# kfly_v3_2.net
KiCad netlist of a schematic drawn in EAGLE
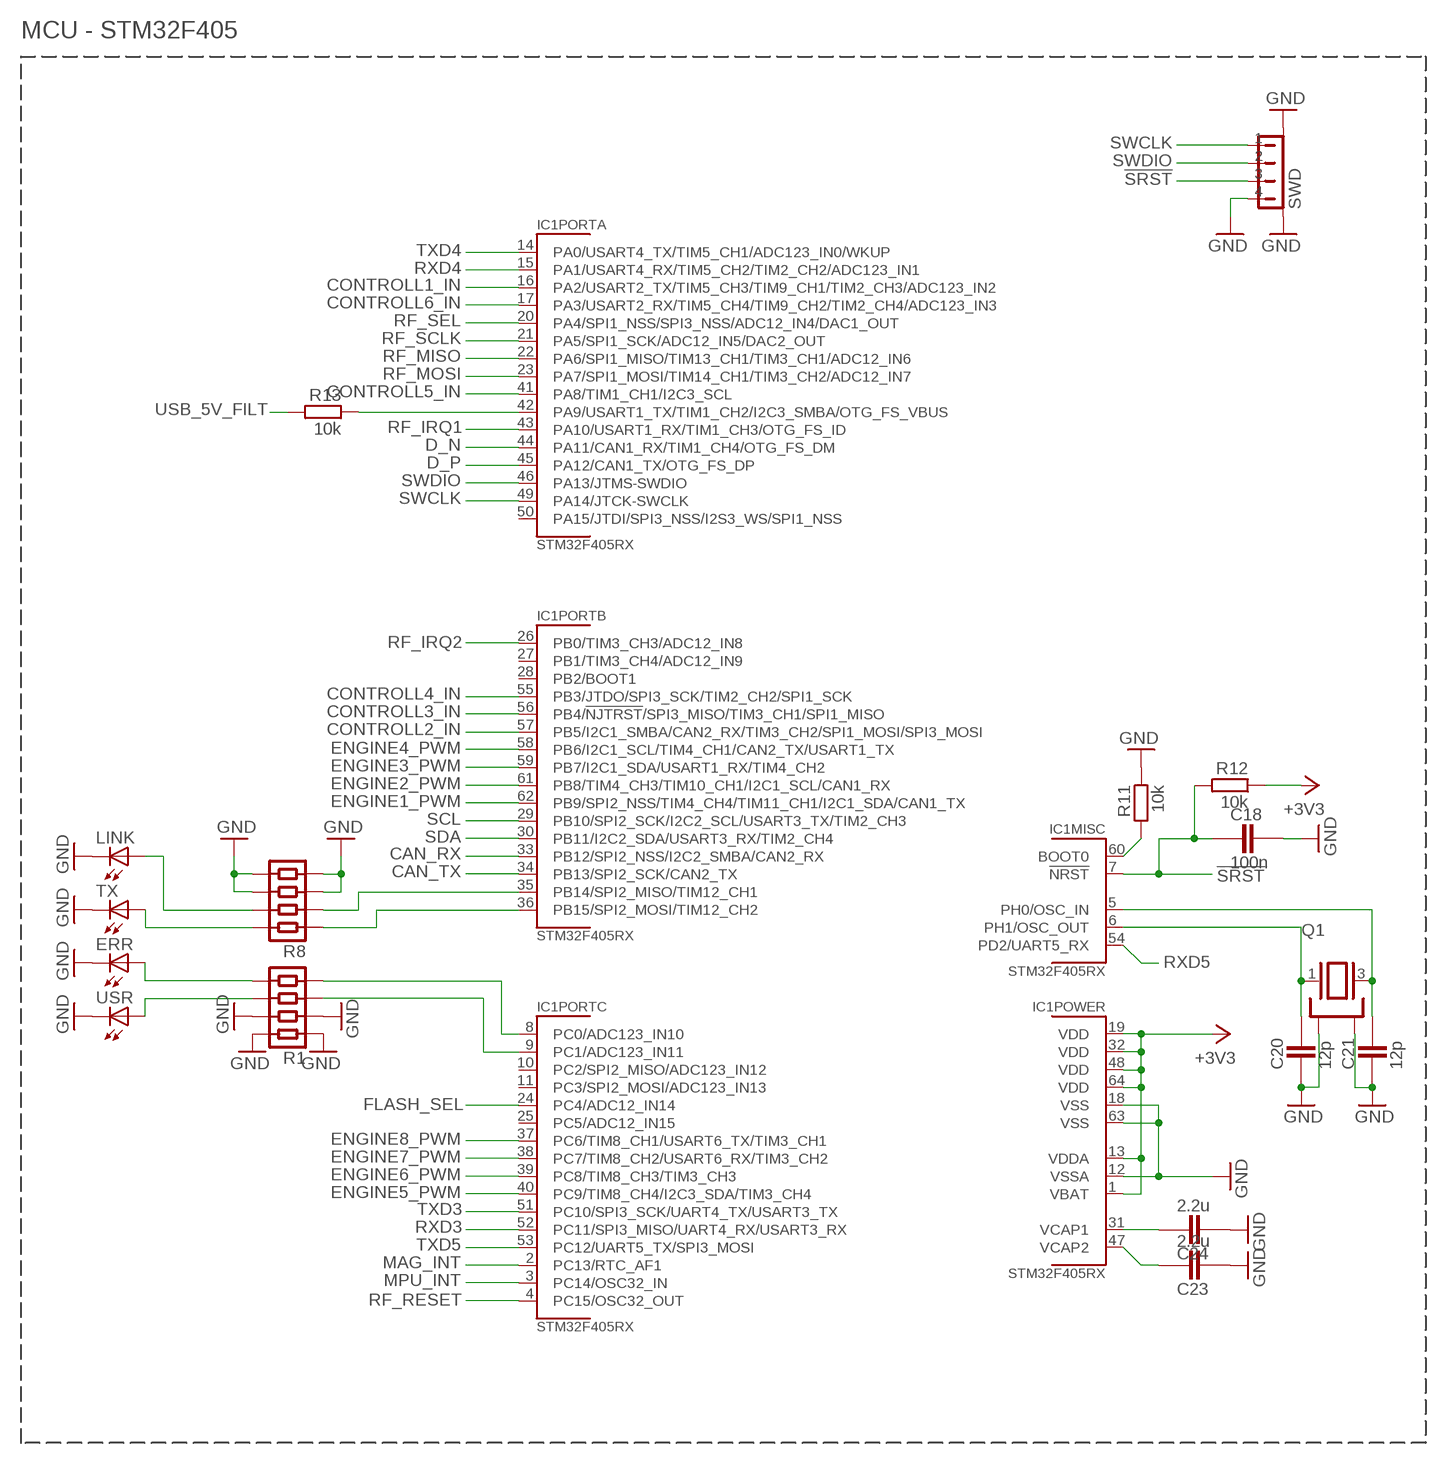
[diagram p0: schematic, sheet 1]
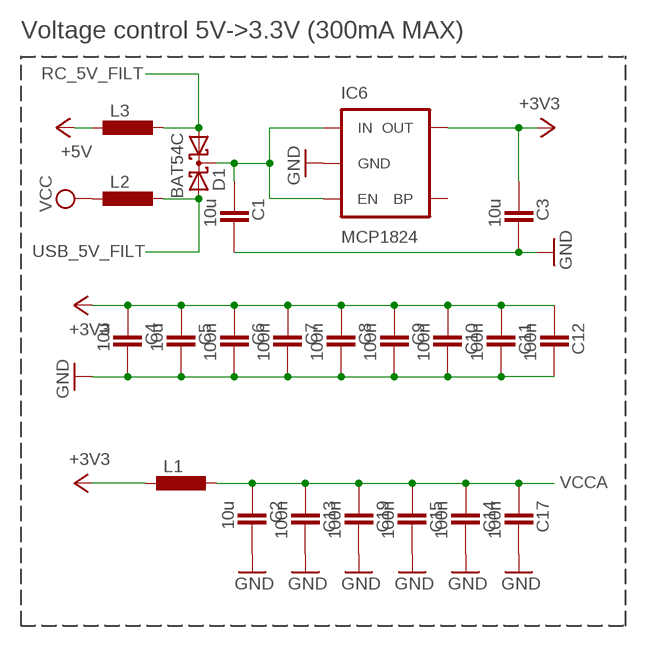
[diagram p1: schematic, sheet 2]
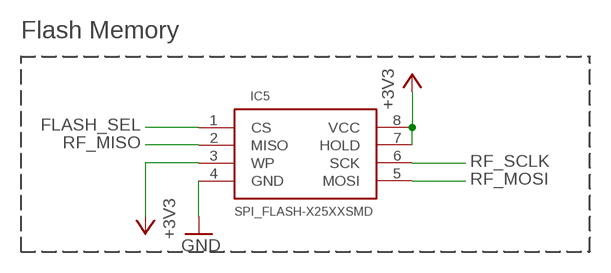
[diagram p2: schematic, sheet 3]
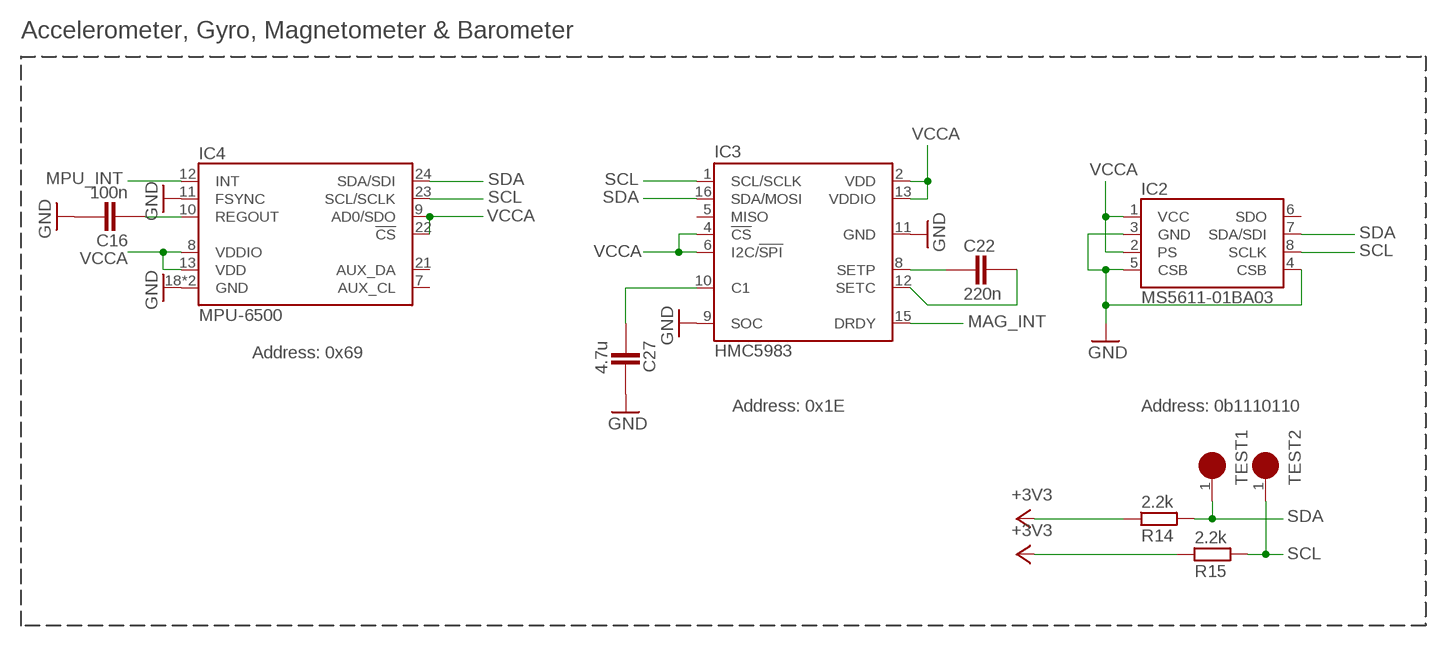
[diagram p3: schematic, sheet 4]
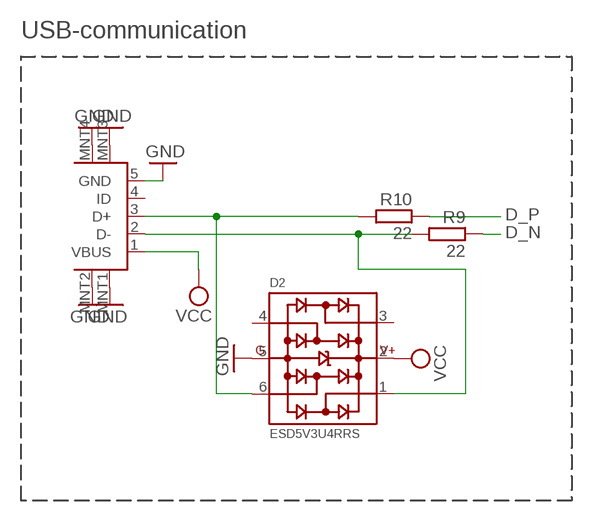
[diagram p4: schematic, sheet 5]
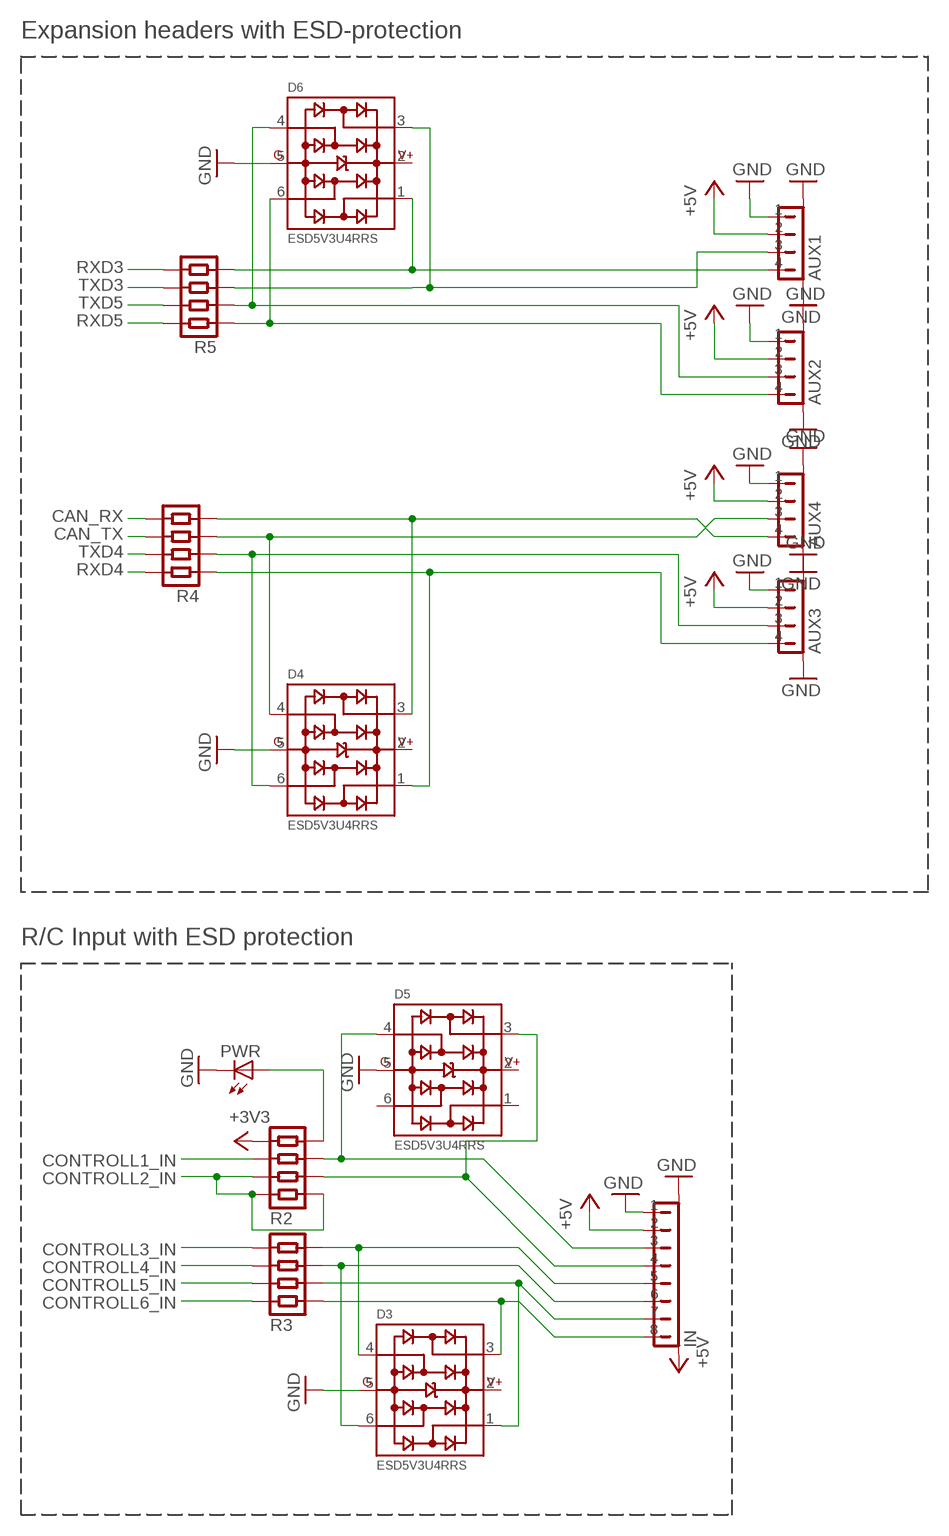
[diagram p5: schematic, sheet 6]
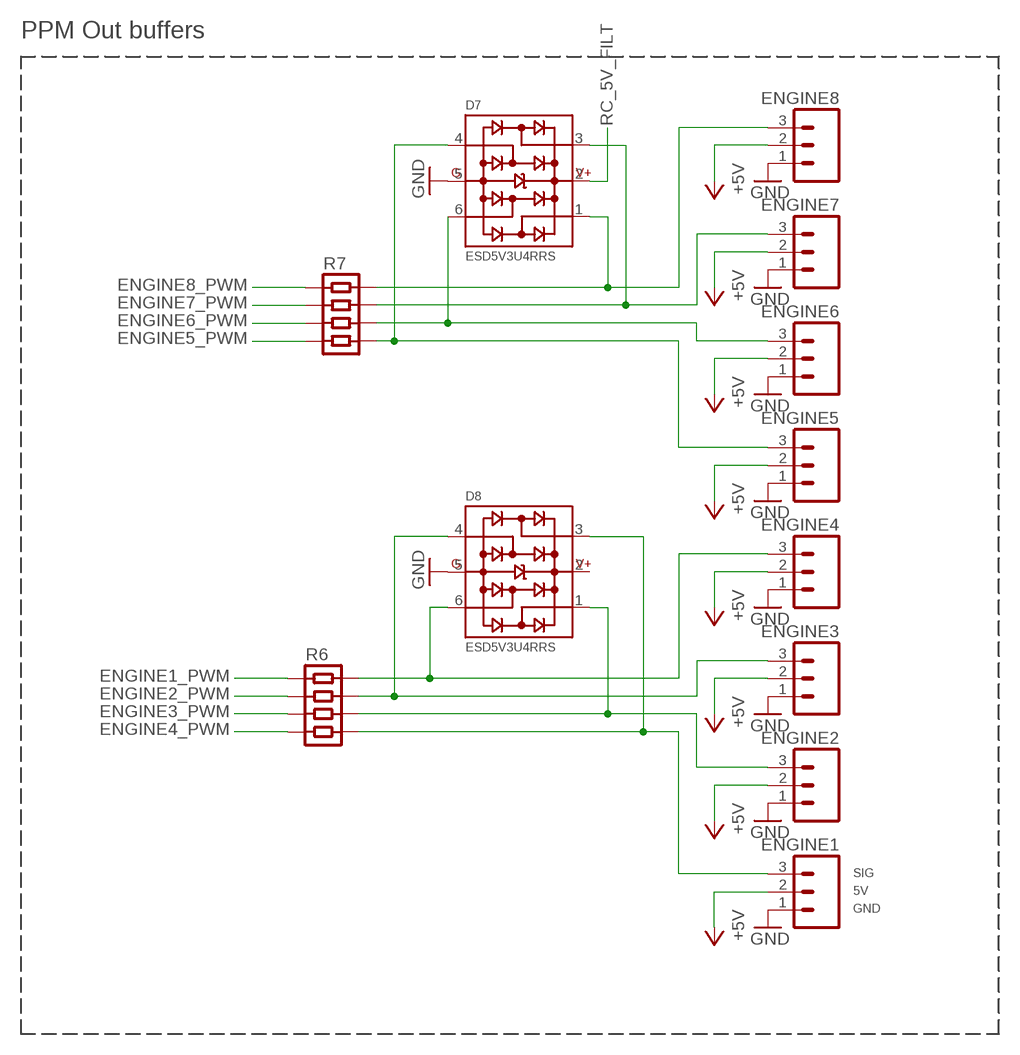
[diagram p6: schematic, sheet 7]
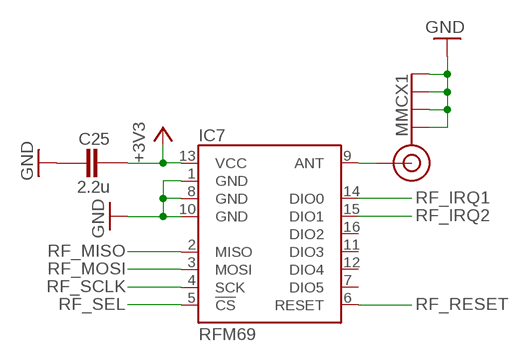
[diagram p7: schematic, sheet 8]

(export (version "E")
  (design (tool "Eeschema 10.0.6"))
  (components
    (comp (ref "C1")
      (value "10u")
      (footprint "eagle-import:CAPC1608X92N")
      (libsource (lib "eagle-import") (part "CAPACITOR_0603"))
    )
    (comp (ref "C2")
      (value "10u")
      (footprint "eagle-import:CAPC1608X92N")
      (libsource (lib "eagle-import") (part "CAPACITOR_0603"))
    )
    (comp (ref "C3")
      (value "10u")
      (footprint "eagle-import:CAPC1608X92N")
      (libsource (lib "eagle-import") (part "CAPACITOR_0603"))
    )
    (comp (ref "C4")
      (value "10u")
      (footprint "eagle-import:CAPC1608X92N")
      (libsource (lib "eagle-import") (part "CAPACITOR_0603"))
    )
    (comp (ref "C5")
      (value "10u")
      (footprint "eagle-import:CAPC1608X92N")
      (libsource (lib "eagle-import") (part "CAPACITOR_0603"))
    )
    (comp (ref "C6")
      (value "100n")
      (footprint "eagle-import:CAPC1005X60N")
      (libsource (lib "eagle-import") (part "CAPACITOR_0402"))
    )
    (comp (ref "C7")
      (value "100n")
      (footprint "eagle-import:CAPC1005X60N")
      (libsource (lib "eagle-import") (part "CAPACITOR_0402"))
    )
    (comp (ref "C8")
      (value "100n")
      (footprint "eagle-import:CAPC1005X60N")
      (libsource (lib "eagle-import") (part "CAPACITOR_0402"))
    )
    (comp (ref "C9")
      (value "100n")
      (footprint "eagle-import:CAPC1005X60N")
      (libsource (lib "eagle-import") (part "CAPACITOR_0402"))
    )
    (comp (ref "C10")
      (value "100n")
      (footprint "eagle-import:CAPC1005X60N")
      (libsource (lib "eagle-import") (part "CAPACITOR_0402"))
    )
    (comp (ref "C11")
      (value "100n")
      (footprint "eagle-import:CAPC1005X60N")
      (libsource (lib "eagle-import") (part "CAPACITOR_0402"))
    )
    (comp (ref "C12")
      (value "100n")
      (footprint "eagle-import:CAPC1005X60N")
      (libsource (lib "eagle-import") (part "CAPACITOR_0402"))
    )
    (comp (ref "C13")
      (value "100n")
      (footprint "eagle-import:CAPC1005X60N")
      (libsource (lib "eagle-import") (part "CAPACITOR_0402"))
    )
    (comp (ref "C14")
      (value "100n")
      (footprint "eagle-import:CAPC1005X60N")
      (libsource (lib "eagle-import") (part "CAPACITOR_0402"))
    )
    (comp (ref "C15")
      (value "100n")
      (footprint "eagle-import:CAPC1005X60N")
      (libsource (lib "eagle-import") (part "CAPACITOR_0402"))
    )
    (comp (ref "C17")
      (value "100n")
      (footprint "eagle-import:CAPC1005X60N")
      (libsource (lib "eagle-import") (part "CAPACITOR_0402"))
    )
    (comp (ref "C19")
      (value "100n")
      (footprint "eagle-import:CAPC1005X60N")
      (libsource (lib "eagle-import") (part "CAPACITOR_0402"))
    )
    (comp (ref "D1")
      (value "BAT54C")
      (footprint "eagle-import:SOT23")
      (libsource (lib "eagle-import") (part "BAT54C"))
    )
    (comp (ref "IC6")
      (value "MCP1824")
      (footprint "eagle-import:SOT23-5")
      (libsource (lib "eagle-import") (part "V_REG_LDOSMD"))
    )
    (comp (ref "L1")
      (value "INDUCTOR_0603")
      (footprint "eagle-import:INDC1608X95N")
      (libsource (lib "eagle-import") (part "INDUCTOR_0603"))
    )
    (comp (ref "L2")
      (value "INDUCTOR_0603")
      (footprint "eagle-import:INDC1608X95N")
      (libsource (lib "eagle-import") (part "INDUCTOR_0603"))
    )
    (comp (ref "L3")
      (value "INDUCTOR_0603")
      (footprint "eagle-import:INDC1608X95N")
      (libsource (lib "eagle-import") (part "INDUCTOR_0603"))
    )
    (comp (ref "AUX1")
      (value "JST-4PIN-SIDE-1.0")
      (footprint "eagle-import:JST-4PIN-SIDE")
      (libsource (lib "eagle-import") (part "JST-4PIN-SIDE-1.0"))
    )
    (comp (ref "AUX2")
      (value "JST-4PIN-SIDE-1.0")
      (footprint "eagle-import:JST-4PIN-SIDE")
      (libsource (lib "eagle-import") (part "JST-4PIN-SIDE-1.0"))
    )
    (comp (ref "AUX3")
      (value "JST-4PIN-SIDE-1.0")
      (footprint "eagle-import:JST-4PIN-SIDE")
      (libsource (lib "eagle-import") (part "JST-4PIN-SIDE-1.0"))
    )
    (comp (ref "AUX4")
      (value "JST-4PIN-SIDE-1.0")
      (footprint "eagle-import:JST-4PIN-SIDE")
      (libsource (lib "eagle-import") (part "JST-4PIN-SIDE-1.0"))
    )
    (comp (ref "D3")
      (value "ESD5V3U4RRS")
      (footprint "eagle-import:SOT363")
      (libsource (lib "eagle-import") (part "ESD5V3U4RRS"))
    )
    (comp (ref "D4")
      (value "ESD5V3U4RRS")
      (footprint "eagle-import:SOT363")
      (libsource (lib "eagle-import") (part "ESD5V3U4RRS"))
    )
    (comp (ref "D5")
      (value "ESD5V3U4RRS")
      (footprint "eagle-import:SOT363")
      (libsource (lib "eagle-import") (part "ESD5V3U4RRS"))
    )
    (comp (ref "D6")
      (value "ESD5V3U4RRS")
      (footprint "eagle-import:SOT363")
      (libsource (lib "eagle-import") (part "ESD5V3U4RRS"))
    )
    (comp (ref "IN")
      (value "JST-8PIN-SIDE-1.0")
      (footprint "eagle-import:JST-8PIN-SIDE")
      (libsource (lib "eagle-import") (part "JST-8PIN-SIDE-1.0"))
    )
    (comp (ref "PWR")
      (value "LED0603")
      (footprint "eagle-import:LED-0603")
      (libsource (lib "eagle-import") (part "LED0603"))
    )
    (comp (ref "R2")
      (value "RESISTOR-4ARRAY-0804")
      (footprint "eagle-import:RESISTORARRAY_0804")
      (libsource (lib "eagle-import") (part "RESISTOR-4ARRAY-0804"))
    )
    (comp (ref "R3")
      (value "RESISTOR-4ARRAY-0804")
      (footprint "eagle-import:RESISTORARRAY_0804")
      (libsource (lib "eagle-import") (part "RESISTOR-4ARRAY-0804"))
    )
    (comp (ref "R4")
      (value "RESISTOR-4ARRAY-0804")
      (footprint "eagle-import:RESISTORARRAY_0804")
      (libsource (lib "eagle-import") (part "RESISTOR-4ARRAY-0804"))
    )
    (comp (ref "R5")
      (value "RESISTOR-4ARRAY-0804")
      (footprint "eagle-import:RESISTORARRAY_0804")
      (libsource (lib "eagle-import") (part "RESISTOR-4ARRAY-0804"))
    )
    (comp (ref "C16")
      (value "100n")
      (footprint "eagle-import:CAPC1005X60N")
      (libsource (lib "eagle-import") (part "CAPACITOR_0402"))
    )
    (comp (ref "C22")
      (value "220n")
      (footprint "eagle-import:CAPC1608X92N")
      (libsource (lib "eagle-import") (part "CAPACITOR_0603"))
    )
    (comp (ref "C27")
      (value "4.7u")
      (footprint "eagle-import:CAPC1608X92N")
      (libsource (lib "eagle-import") (part "CAPACITOR_0603"))
    )
    (comp (ref "IC2")
      (value "MS5611-01BA03")
      (footprint "eagle-import:MS5611")
      (libsource (lib "eagle-import") (part "MS5611-01BA01"))
    )
    (comp (ref "IC3")
      (value "HMC5983")
      (footprint "eagle-import:LPCC16")
      (libsource (lib "eagle-import") (part "HMC5983"))
    )
    (comp (ref "IC4")
      (value "MPU-6500")
      (footprint "eagle-import:QFN-24-3X3MM")
      (libsource (lib "eagle-import") (part "MPU-6500"))
    )
    (comp (ref "R14")
      (value "2.2k")
      (footprint "eagle-import:RESC1005X40AN")
      (libsource (lib "eagle-import") (part "RESISTOR_0402"))
    )
    (comp (ref "R15")
      (value "2.2k")
      (footprint "eagle-import:RESC1005X40AN")
      (libsource (lib "eagle-import") (part "RESISTOR_0402"))
    )
    (comp (ref "TEST1")
      (value "TESTPOINT")
      (footprint "eagle-import:TESTPOINT_1.2")
      (libsource (lib "eagle-import") (part "TESTPOINT"))
    )
    (comp (ref "TEST2")
      (value "TESTPOINT")
      (footprint "eagle-import:TESTPOINT_1.2")
      (libsource (lib "eagle-import") (part "TESTPOINT"))
    )
    (comp (ref "C25")
      (value "2.2u")
      (footprint "eagle-import:CAPC1005X60N")
      (libsource (lib "eagle-import") (part "CAPACITOR_0402"))
    )
    (comp (ref "IC7")
      (value "RFM69")
      (footprint "eagle-import:RFM69")
      (libsource (lib "eagle-import") (part "RFM69"))
    )
    (comp (ref "MMCX1")
      (value "MMCX")
      (footprint "eagle-import:MMCX_THROUGHHOLE_RIGHTANGLE")
      (libsource (lib "eagle-import") (part "MMCX"))
    )
    (comp (ref "D7")
      (value "ESD5V3U4RRS")
      (footprint "eagle-import:SOT363")
      (libsource (lib "eagle-import") (part "ESD5V3U4RRS"))
    )
    (comp (ref "D8")
      (value "ESD5V3U4RRS")
      (footprint "eagle-import:SOT363")
      (libsource (lib "eagle-import") (part "ESD5V3U4RRS"))
    )
    (comp (ref "ENGINE1")
      (value "M03TH_90DEG")
      (footprint "eagle-import:M03_90DEG")
      (libsource (lib "eagle-import") (part "M03TH_90DEG"))
    )
    (comp (ref "ENGINE2")
      (value "M03TH_90DEG")
      (footprint "eagle-import:M03_90DEG")
      (libsource (lib "eagle-import") (part "M03TH_90DEG"))
    )
    (comp (ref "ENGINE3")
      (value "M03TH_90DEG")
      (footprint "eagle-import:M03_90DEG")
      (libsource (lib "eagle-import") (part "M03TH_90DEG"))
    )
    (comp (ref "ENGINE4")
      (value "M03TH_90DEG")
      (footprint "eagle-import:M03_90DEG")
      (libsource (lib "eagle-import") (part "M03TH_90DEG"))
    )
    (comp (ref "ENGINE5")
      (value "M03TH_90DEG")
      (footprint "eagle-import:M03_90DEG")
      (libsource (lib "eagle-import") (part "M03TH_90DEG"))
    )
    (comp (ref "ENGINE6")
      (value "M03TH_90DEG")
      (footprint "eagle-import:M03_90DEG")
      (libsource (lib "eagle-import") (part "M03TH_90DEG"))
    )
    (comp (ref "ENGINE7")
      (value "M03TH_90DEG")
      (footprint "eagle-import:M03_90DEG")
      (libsource (lib "eagle-import") (part "M03TH_90DEG"))
    )
    (comp (ref "ENGINE8")
      (value "M03TH_90DEG")
      (footprint "eagle-import:M03_90DEG")
      (libsource (lib "eagle-import") (part "M03TH_90DEG"))
    )
    (comp (ref "R6")
      (value "RESISTOR-4ARRAY-0804")
      (footprint "eagle-import:RESISTORARRAY_0804")
      (libsource (lib "eagle-import") (part "RESISTOR-4ARRAY-0804"))
    )
    (comp (ref "R7")
      (value "RESISTOR-4ARRAY-0804")
      (footprint "eagle-import:RESISTORARRAY_0804")
      (libsource (lib "eagle-import") (part "RESISTOR-4ARRAY-0804"))
    )
    (comp (ref "C18")
      (value "100n")
      (footprint "eagle-import:CAPC1005X60N")
      (libsource (lib "eagle-import") (part "CAPACITOR_0402"))
    )
    (comp (ref "C20")
      (value "12p")
      (footprint "eagle-import:CAPC1005X60N")
      (libsource (lib "eagle-import") (part "CAPACITOR_0402"))
    )
    (comp (ref "C21")
      (value "12p")
      (footprint "eagle-import:CAPC1005X60N")
      (libsource (lib "eagle-import") (part "CAPACITOR_0402"))
    )
    (comp (ref "C23")
      (value "2.2u")
      (footprint "eagle-import:CAPC1005X60N")
      (libsource (lib "eagle-import") (part "CAPACITOR_0402"))
    )
    (comp (ref "C24")
      (value "2.2u")
      (footprint "eagle-import:CAPC1005X60N")
      (libsource (lib "eagle-import") (part "CAPACITOR_0402"))
    )
    (comp (ref "ERR")
      (value "LED0603")
      (footprint "eagle-import:LED-0603")
      (libsource (lib "eagle-import") (part "LED0603"))
    )
    (comp (ref "IC1")
      (value "STM32F405RX")
      (footprint "eagle-import:LQFP64-10X10")
      (libsource (lib "eagle-import") (part "STM32F4X5RX"))
    )
    (comp (ref "LINK")
      (value "LED0603")
      (footprint "eagle-import:LED-0603")
      (libsource (lib "eagle-import") (part "LED0603"))
    )
    (comp (ref "Q1")
      (value "2.5X3.2CRYSTAL")
      (footprint "eagle-import:2.5X3.2CRYSTAL")
      (libsource (lib "eagle-import") (part "2.5X3.2CRYSTAL"))
    )
    (comp (ref "R1")
      (value "RESISTOR-4ARRAY-0804")
      (footprint "eagle-import:RESISTORARRAY_0804")
      (libsource (lib "eagle-import") (part "RESISTOR-4ARRAY-0804"))
    )
    (comp (ref "R8")
      (value "RESISTOR-4ARRAY-0804")
      (footprint "eagle-import:RESISTORARRAY_0804")
      (libsource (lib "eagle-import") (part "RESISTOR-4ARRAY-0804"))
    )
    (comp (ref "R11")
      (value "10k")
      (footprint "eagle-import:RESC1005X40AN")
      (libsource (lib "eagle-import") (part "RESISTOR_0402"))
    )
    (comp (ref "R12")
      (value "10k")
      (footprint "eagle-import:RESC1005X40AN")
      (libsource (lib "eagle-import") (part "RESISTOR_0402"))
    )
    (comp (ref "R13")
      (value "10k")
      (footprint "eagle-import:RESC1005X40AN")
      (libsource (lib "eagle-import") (part "RESISTOR_0402"))
    )
    (comp (ref "SWD")
      (value "JST-4PIN-SIDE-1.0")
      (footprint "eagle-import:JST-4PIN-SIDE")
      (libsource (lib "eagle-import") (part "JST-4PIN-SIDE-1.0"))
    )
    (comp (ref "TX")
      (value "LED0603")
      (footprint "eagle-import:LED-0603")
      (libsource (lib "eagle-import") (part "LED0603"))
    )
    (comp (ref "USR")
      (value "LED0603")
      (footprint "eagle-import:LED-0603")
      (libsource (lib "eagle-import") (part "LED0603"))
    )
    (comp (ref "IC5")
      (value "SPI_FLASH-X25XXSMD")
      (footprint "eagle-import:SO08")
      (libsource (lib "eagle-import") (part "SPI_FLASH-X25XXSMD"))
    )
    (comp (ref "D2")
      (value "ESD5V3U4RRS")
      (footprint "eagle-import:SOT363")
      (libsource (lib "eagle-import") (part "ESD5V3U4RRS"))
    )
    (comp (ref "R9")
      (value "22")
      (footprint "eagle-import:RESC1005X40AN")
      (libsource (lib "eagle-import") (part "RESISTOR_0402"))
    )
    (comp (ref "R10")
      (value "22")
      (footprint "eagle-import:RESC1005X40AN")
      (libsource (lib "eagle-import") (part "RESISTOR_0402"))
    )
    (comp (ref "USB1")
      (value "USB-MICRO-B-BOTTOM")
      (footprint "eagle-import:MICROUSB_TYPEB_SURFACE")
      (libsource (lib "eagle-import") (part "USB-MICRO-B-BOTTOM"))
    )
  )
  (nets
    (net (code "1") (name "+3V3") (class "Default")
      (node (ref "C10") (pin "1") (pinfunction "1_1") (pintype "passive"))
      (node (ref "C11") (pin "1") (pinfunction "1_1") (pintype "passive"))
      (node (ref "C12") (pin "1") (pinfunction "1_1") (pintype "passive"))
      (node (ref "C25") (pin "1") (pinfunction "1_1") (pintype "passive"))
      (node (ref "C3") (pin "1") (pinfunction "1_1") (pintype "passive"))
      (node (ref "C4") (pin "1") (pinfunction "1_1") (pintype "passive"))
      (node (ref "C5") (pin "1") (pinfunction "1_1") (pintype "passive"))
      (node (ref "C6") (pin "1") (pinfunction "1_1") (pintype "passive"))
      (node (ref "C7") (pin "1") (pinfunction "1_1") (pintype "passive"))
      (node (ref "C8") (pin "1") (pinfunction "1_1") (pintype "passive"))
      (node (ref "C9") (pin "1") (pinfunction "1_1") (pintype "passive"))
      (node (ref "IC1") (pin "1") (pinfunction "VBAT_1") (pintype "bidirectional"))
      (node (ref "IC1") (pin "13") (pinfunction "VDDA_13") (pintype "bidirectional"))
      (node (ref "IC1") (pin "19") (pinfunction "VDD_19") (pintype "bidirectional"))
      (node (ref "IC1") (pin "32") (pinfunction "VDD_32") (pintype "bidirectional"))
      (node (ref "IC1") (pin "48") (pinfunction "VDD_48") (pintype "bidirectional"))
      (node (ref "IC1") (pin "64") (pinfunction "VDD_64") (pintype "bidirectional"))
      (node (ref "IC5") (pin "3") (pinfunction "WP_3") (pintype "bidirectional"))
      (node (ref "IC5") (pin "7") (pinfunction "HOLD_7") (pintype "bidirectional"))
      (node (ref "IC5") (pin "8") (pinfunction "VCC_8") (pintype "bidirectional"))
      (node (ref "IC6") (pin "5") (pinfunction "OUT_5") (pintype "passive"))
      (node (ref "IC7") (pin "13") (pinfunction "VCC_13") (pintype "bidirectional"))
      (node (ref "L1") (pin "1") (pinfunction "1_1") (pintype "passive"))
      (node (ref "R12") (pin "1") (pinfunction "1_1") (pintype "passive"))
      (node (ref "R14") (pin "1") (pinfunction "1_1") (pintype "passive"))
      (node (ref "R15") (pin "1") (pinfunction "1_1") (pintype "passive"))
      (node (ref "R2") (pin "4") (pinfunction "4_4") (pintype "bidirectional"))
    )
    (net (code "2") (name "+5V") (class "Default")
      (node (ref "AUX1") (pin "2") (pinfunction "2_2") (pintype "bidirectional"))
      (node (ref "AUX2") (pin "2") (pinfunction "2_2") (pintype "bidirectional"))
      (node (ref "AUX3") (pin "2") (pinfunction "2_2") (pintype "bidirectional"))
      (node (ref "AUX4") (pin "2") (pinfunction "2_2") (pintype "bidirectional"))
      (node (ref "ENGINE1") (pin "2") (pinfunction "2_2") (pintype "passive"))
      (node (ref "ENGINE2") (pin "2") (pinfunction "2_2") (pintype "passive"))
      (node (ref "ENGINE3") (pin "2") (pinfunction "2_2") (pintype "passive"))
      (node (ref "ENGINE4") (pin "2") (pinfunction "2_2") (pintype "passive"))
      (node (ref "ENGINE5") (pin "2") (pinfunction "2_2") (pintype "passive"))
      (node (ref "ENGINE6") (pin "2") (pinfunction "2_2") (pintype "passive"))
      (node (ref "ENGINE7") (pin "2") (pinfunction "2_2") (pintype "passive"))
      (node (ref "ENGINE8") (pin "2") (pinfunction "2_2") (pintype "passive"))
      (node (ref "IN") (pin "2") (pinfunction "2_2") (pintype "bidirectional"))
      (node (ref "IN") (pin "NC2") (pinfunction "GND2_NC2") (pintype "bidirectional"))
      (node (ref "L3") (pin "1") (pinfunction "1_1") (pintype "passive"))
    )
    (net (code "3") (name "CAN_RX") (class "Default")
      (node (ref "IC1") (pin "33") (pinfunction "PB12/SPI2_NSS/I2C2_SMBA/CAN2_RX_33") (pintype "bidirectional"))
      (node (ref "R4") (pin "5") (pinfunction "5_5") (pintype "bidirectional"))
    )
    (net (code "4") (name "CAN_TX") (class "Default")
      (node (ref "IC1") (pin "34") (pinfunction "PB13/SPI2_SCK/CAN2_TX_34") (pintype "bidirectional"))
      (node (ref "R4") (pin "6") (pinfunction "6_6") (pintype "bidirectional"))
    )
    (net (code "5") (name "CONTROLL1_IN") (class "Default")
      (node (ref "IC1") (pin "16") (pinfunction "PA2/USART2_TX/TIM5_CH3/TIM9_CH1/TIM2_CH3/ADC123_IN2_16") (pintype "bidirectional"))
      (node (ref "R2") (pin "3") (pinfunction "3_3") (pintype "bidirectional"))
    )
    (net (code "6") (name "CONTROLL2_IN") (class "Default")
      (node (ref "IC1") (pin "57") (pinfunction "PB5/I2C1_SMBA/CAN2_RX/TIM3_CH2/SPI1_MOSI/SPI3_MOSI_57") (pintype "bidirectional"))
      (node (ref "R2") (pin "1") (pinfunction "1_1") (pintype "bidirectional"))
      (node (ref "R2") (pin "2") (pinfunction "2_2") (pintype "bidirectional"))
      (node (ref "R2") (pin "8") (pinfunction "8_8") (pintype "bidirectional"))
    )
    (net (code "7") (name "CONTROLL3_IN") (class "Default")
      (node (ref "IC1") (pin "56") (pinfunction "PB4/~{NJTRST}/SPI3_MISO/TIM3_CH1/SPI1_MISO_56") (pintype "bidirectional"))
      (node (ref "R3") (pin "4") (pinfunction "4_4") (pintype "bidirectional"))
    )
    (net (code "8") (name "CONTROLL4_IN") (class "Default")
      (node (ref "IC1") (pin "55") (pinfunction "PB3/JTDO/SPI3_SCK/TIM2_CH2/SPI1_SCK_55") (pintype "bidirectional"))
      (node (ref "R3") (pin "3") (pinfunction "3_3") (pintype "bidirectional"))
    )
    (net (code "9") (name "CONTROLL5_IN") (class "Default")
      (node (ref "IC1") (pin "41") (pinfunction "PA8/TIM1_CH1/I2C3_SCL_41") (pintype "bidirectional"))
      (node (ref "R3") (pin "2") (pinfunction "2_2") (pintype "bidirectional"))
    )
    (net (code "10") (name "CONTROLL6_IN") (class "Default")
      (node (ref "IC1") (pin "17") (pinfunction "PA3/USART2_RX/TIM5_CH4/TIM9_CH2/TIM2_CH4/ADC123_IN3_17") (pintype "bidirectional"))
      (node (ref "R3") (pin "1") (pinfunction "1_1") (pintype "bidirectional"))
    )
    (net (code "11") (name "D_N") (class "Default")
      (node (ref "IC1") (pin "44") (pinfunction "PA11/CAN1_RX/TIM1_CH4/OTG_FS_DM_44") (pintype "bidirectional"))
      (node (ref "R9") (pin "1") (pinfunction "1_1") (pintype "passive"))
    )
    (net (code "12") (name "D_P") (class "Default")
      (node (ref "IC1") (pin "45") (pinfunction "PA12/CAN1_TX/OTG_FS_DP_45") (pintype "bidirectional"))
      (node (ref "R10") (pin "1") (pinfunction "1_1") (pintype "passive"))
    )
    (net (code "13") (name "ENGINE1_PWM") (class "Default")
      (node (ref "IC1") (pin "62") (pinfunction "PB9/SPI2_NSS/TIM4_CH4/TIM11_CH1/I2C1_SDA/CAN1_TX_62") (pintype "bidirectional"))
      (node (ref "R6") (pin "1") (pinfunction "1_1") (pintype "bidirectional"))
    )
    (net (code "14") (name "ENGINE2_PWM") (class "Default")
      (node (ref "IC1") (pin "61") (pinfunction "PB8/TIM4_CH3/TIM10_CH1/I2C1_SCL/CAN1_RX_61") (pintype "bidirectional"))
      (node (ref "R6") (pin "2") (pinfunction "2_2") (pintype "bidirectional"))
    )
    (net (code "15") (name "ENGINE3_PWM") (class "Default")
      (node (ref "IC1") (pin "59") (pinfunction "PB7/I2C1_SDA/USART1_RX/TIM4_CH2_59") (pintype "bidirectional"))
      (node (ref "R6") (pin "3") (pinfunction "3_3") (pintype "bidirectional"))
    )
    (net (code "16") (name "ENGINE4_PWM") (class "Default")
      (node (ref "IC1") (pin "58") (pinfunction "PB6/I2C1_SCL/TIM4_CH1/CAN2_TX/USART1_TX_58") (pintype "bidirectional"))
      (node (ref "R6") (pin "4") (pinfunction "4_4") (pintype "bidirectional"))
    )
    (net (code "17") (name "ENGINE5_PWM") (class "Default")
      (node (ref "IC1") (pin "40") (pinfunction "PC9/TIM8_CH4/I2C3_SDA/TIM3_CH4_40") (pintype "bidirectional"))
      (node (ref "R7") (pin "4") (pinfunction "4_4") (pintype "bidirectional"))
    )
    (net (code "18") (name "ENGINE6_PWM") (class "Default")
      (node (ref "IC1") (pin "39") (pinfunction "PC8/TIM8_CH3/TIM3_CH3_39") (pintype "bidirectional"))
      (node (ref "R7") (pin "3") (pinfunction "3_3") (pintype "bidirectional"))
    )
    (net (code "19") (name "ENGINE7_PWM") (class "Default")
      (node (ref "IC1") (pin "38") (pinfunction "PC7/TIM8_CH2/USART6_RX/TIM3_CH2_38") (pintype "bidirectional"))
      (node (ref "R7") (pin "2") (pinfunction "2_2") (pintype "bidirectional"))
    )
    (net (code "20") (name "ENGINE8_PWM") (class "Default")
      (node (ref "IC1") (pin "37") (pinfunction "PC6/TIM8_CH1/USART6_TX/TIM3_CH1_37") (pintype "bidirectional"))
      (node (ref "R7") (pin "1") (pinfunction "1_1") (pintype "bidirectional"))
    )
    (net (code "21") (name "FLASH_SEL") (class "Default")
      (node (ref "IC1") (pin "24") (pinfunction "PC4/ADC12_IN14_24") (pintype "bidirectional"))
      (node (ref "IC5") (pin "1") (pinfunction "CS_1") (pintype "bidirectional"))
    )
    (net (code "22") (name "GND") (class "Default")
      (node (ref "AUX1") (pin "1") (pinfunction "1_1") (pintype "bidirectional"))
      (node (ref "AUX1") (pin "NC1") (pinfunction "P1_NC1") (pintype "bidirectional"))
      (node (ref "AUX1") (pin "NC2") (pinfunction "P2_NC2") (pintype "bidirectional"))
      (node (ref "AUX2") (pin "1") (pinfunction "1_1") (pintype "bidirectional"))
      (node (ref "AUX2") (pin "NC1") (pinfunction "P1_NC1") (pintype "bidirectional"))
      (node (ref "AUX2") (pin "NC2") (pinfunction "P2_NC2") (pintype "bidirectional"))
      (node (ref "AUX3") (pin "1") (pinfunction "1_1") (pintype "bidirectional"))
      (node (ref "AUX3") (pin "NC1") (pinfunction "P1_NC1") (pintype "bidirectional"))
      (node (ref "AUX3") (pin "NC2") (pinfunction "P2_NC2") (pintype "bidirectional"))
      (node (ref "AUX4") (pin "1") (pinfunction "1_1") (pintype "bidirectional"))
      (node (ref "AUX4") (pin "NC1") (pinfunction "P1_NC1") (pintype "bidirectional"))
      (node (ref "AUX4") (pin "NC2") (pinfunction "P2_NC2") (pintype "bidirectional"))
      (node (ref "C1") (pin "2") (pinfunction "2_2") (pintype "passive"))
      (node (ref "C10") (pin "2") (pinfunction "2_2") (pintype "passive"))
      (node (ref "C11") (pin "2") (pinfunction "2_2") (pintype "passive"))
      (node (ref "C12") (pin "2") (pinfunction "2_2") (pintype "passive"))
      (node (ref "C13") (pin "2") (pinfunction "2_2") (pintype "passive"))
      (node (ref "C14") (pin "2") (pinfunction "2_2") (pintype "passive"))
      (node (ref "C15") (pin "2") (pinfunction "2_2") (pintype "passive"))
      (node (ref "C16") (pin "2") (pinfunction "2_2") (pintype "passive"))
      (node (ref "C17") (pin "2") (pinfunction "2_2") (pintype "passive"))
      (node (ref "C18") (pin "2") (pinfunction "2_2") (pintype "passive"))
      (node (ref "C19") (pin "2") (pinfunction "2_2") (pintype "passive"))
      (node (ref "C2") (pin "2") (pinfunction "2_2") (pintype "passive"))
      (node (ref "C20") (pin "1") (pinfunction "1_1") (pintype "passive"))
      (node (ref "C21") (pin "1") (pinfunction "1_1") (pintype "passive"))
      (node (ref "C23") (pin "2") (pinfunction "2_2") (pintype "passive"))
      (node (ref "C24") (pin "2") (pinfunction "2_2") (pintype "passive"))
      (node (ref "C25") (pin "2") (pinfunction "2_2") (pintype "passive"))
      (node (ref "C27") (pin "2") (pinfunction "2_2") (pintype "passive"))
      (node (ref "C3") (pin "2") (pinfunction "2_2") (pintype "passive"))
      (node (ref "C4") (pin "2") (pinfunction "2_2") (pintype "passive"))
      (node (ref "C5") (pin "2") (pinfunction "2_2") (pintype "passive"))
      (node (ref "C6") (pin "2") (pinfunction "2_2") (pintype "passive"))
      (node (ref "C7") (pin "2") (pinfunction "2_2") (pintype "passive"))
      (node (ref "C8") (pin "2") (pinfunction "2_2") (pintype "passive"))
      (node (ref "C9") (pin "2") (pinfunction "2_2") (pintype "passive"))
      (node (ref "D2") (pin "5") (pinfunction "5_5") (pintype "bidirectional"))
      (node (ref "D3") (pin "5") (pinfunction "5_5") (pintype "bidirectional"))
      (node (ref "D4") (pin "5") (pinfunction "5_5") (pintype "bidirectional"))
      (node (ref "D5") (pin "5") (pinfunction "5_5") (pintype "bidirectional"))
      (node (ref "D6") (pin "5") (pinfunction "5_5") (pintype "bidirectional"))
      (node (ref "D7") (pin "5") (pinfunction "5_5") (pintype "bidirectional"))
      (node (ref "D8") (pin "5") (pinfunction "5_5") (pintype "bidirectional"))
      (node (ref "ENGINE1") (pin "1") (pinfunction "1_1") (pintype "passive"))
      (node (ref "ENGINE2") (pin "1") (pinfunction "1_1") (pintype "passive"))
      (node (ref "ENGINE3") (pin "1") (pinfunction "1_1") (pintype "passive"))
      (node (ref "ENGINE4") (pin "1") (pinfunction "1_1") (pintype "passive"))
      (node (ref "ENGINE5") (pin "1") (pinfunction "1_1") (pintype "passive"))
      (node (ref "ENGINE6") (pin "1") (pinfunction "1_1") (pintype "passive"))
      (node (ref "ENGINE7") (pin "1") (pinfunction "1_1") (pintype "passive"))
      (node (ref "ENGINE8") (pin "1") (pinfunction "1_1") (pintype "passive"))
      (node (ref "ERR") (pin "C") (pinfunction "C_C") (pintype "passive"))
      (node (ref "IC1") (pin "12") (pinfunction "VSSA_12") (pintype "bidirectional"))
      (node (ref "IC1") (pin "18") (pinfunction "VSS_18") (pintype "bidirectional"))
      (node (ref "IC1") (pin "63") (pinfunction "VSS_63") (pintype "bidirectional"))
      (node (ref "IC2") (pin "3") (pinfunction "GND_3") (pintype "bidirectional"))
      (node (ref "IC2") (pin "4") (pinfunction "CSB_4") (pintype "bidirectional"))
      (node (ref "IC2") (pin "5") (pinfunction "CSB_5") (pintype "bidirectional"))
      (node (ref "IC3") (pin "11") (pinfunction "GND_11") (pintype "bidirectional"))
      (node (ref "IC3") (pin "9") (pinfunction "SOC_9") (pintype "bidirectional"))
      (node (ref "IC4") (pin "11") (pinfunction "FSYNC_11") (pintype "bidirectional"))
      (node (ref "IC4") (pin "18") (pinfunction "GND_18") (pintype "power_in"))
      (node (ref "IC4") (pin "20") (pinfunction "GND_20") (pintype "power_in"))
      (node (ref "IC5") (pin "4") (pinfunction "GND_4") (pintype "bidirectional"))
      (node (ref "IC6") (pin "2") (pinfunction "GND_2") (pintype "input"))
      (node (ref "IC7") (pin "1") (pinfunction "GND_1") (pintype "bidirectional"))
      (node (ref "IC7") (pin "10") (pinfunction "GND_10") (pintype "bidirectional"))
      (node (ref "IC7") (pin "8") (pinfunction "GND_8") (pintype "bidirectional"))
      (node (ref "IN") (pin "1") (pinfunction "1_1") (pintype "bidirectional"))
      (node (ref "IN") (pin "NC1") (pinfunction "GND1_NC1") (pintype "bidirectional"))
      (node (ref "LINK") (pin "C") (pinfunction "C_C") (pintype "passive"))
      (node (ref "MMCX1") (pin "G1") (pinfunction "GND_G1") (pintype "bidirectional"))
      (node (ref "MMCX1") (pin "G2") (pinfunction "GND_G2") (pintype "bidirectional"))
      (node (ref "MMCX1") (pin "G3") (pinfunction "GND_G3") (pintype "bidirectional"))
      (node (ref "MMCX1") (pin "G4") (pinfunction "GND_G4") (pintype "bidirectional"))
      (node (ref "PWR") (pin "C") (pinfunction "C_C") (pintype "passive"))
      (node (ref "Q1") (pin "2") (pinfunction "P$1_2") (pintype "bidirectional"))
      (node (ref "Q1") (pin "4") (pinfunction "P$2_4") (pintype "bidirectional"))
      (node (ref "R1") (pin "1") (pinfunction "1_1") (pintype "bidirectional"))
      (node (ref "R1") (pin "2") (pinfunction "2_2") (pintype "bidirectional"))
      (node (ref "R1") (pin "7") (pinfunction "7_7") (pintype "bidirectional"))
      (node (ref "R1") (pin "8") (pinfunction "8_8") (pintype "bidirectional"))
      (node (ref "R11") (pin "1") (pinfunction "1_1") (pintype "passive"))
      (node (ref "R8") (pin "3") (pinfunction "3_3") (pintype "bidirectional"))
      (node (ref "R8") (pin "4") (pinfunction "4_4") (pintype "bidirectional"))
      (node (ref "R8") (pin "5") (pinfunction "5_5") (pintype "bidirectional"))
      (node (ref "R8") (pin "6") (pinfunction "6_6") (pintype "bidirectional"))
      (node (ref "SWD") (pin "4") (pinfunction "4_4") (pintype "bidirectional"))
      (node (ref "SWD") (pin "NC1") (pinfunction "P1_NC1") (pintype "bidirectional"))
      (node (ref "SWD") (pin "NC2") (pinfunction "P2_NC2") (pintype "bidirectional"))
      (node (ref "TX") (pin "C") (pinfunction "C_C") (pintype "passive"))
      (node (ref "USB1") (pin "5") (pinfunction "GND_5") (pintype "bidirectional"))
      (node (ref "USB1") (pin "MNT1") (pinfunction "MTN1_MNT1") (pintype "bidirectional"))
      (node (ref "USB1") (pin "MNT2") (pinfunction "MTN2_MNT2") (pintype "bidirectional"))
      (node (ref "USB1") (pin "MNT3") (pinfunction "MTN3_MNT3") (pintype "bidirectional"))
      (node (ref "USB1") (pin "MNT4") (pinfunction "MTN4_MNT4") (pintype "bidirectional"))
      (node (ref "USR") (pin "C") (pinfunction "C_C") (pintype "passive"))
    )
    (net (code "23") (name "MAG_INT") (class "Default")
      (node (ref "IC1") (pin "2") (pinfunction "PC13/RTC_AF1_2") (pintype "bidirectional"))
      (node (ref "IC3") (pin "15") (pinfunction "DRDY_15") (pintype "bidirectional"))
    )
    (net (code "24") (name "MPU_INT") (class "Default")
      (node (ref "IC1") (pin "3") (pinfunction "PC14/OSC32_IN_3") (pintype "bidirectional"))
      (node (ref "IC4") (pin "12") (pinfunction "INT_12") (pintype "bidirectional"))
    )
    (net (code "25") (name "Net-(AUX1-Pad3)") (class "Default")
      (node (ref "AUX1") (pin "3") (pinfunction "3_3") (pintype "bidirectional"))
      (node (ref "D6") (pin "3") (pinfunction "3_3") (pintype "bidirectional"))
      (node (ref "R5") (pin "3") (pinfunction "3_3") (pintype "bidirectional"))
    )
    (net (code "26") (name "Net-(AUX1-Pad4)") (class "Default")
      (node (ref "AUX1") (pin "4") (pinfunction "4_4") (pintype "bidirectional"))
      (node (ref "D6") (pin "1") (pinfunction "1_1") (pintype "bidirectional"))
      (node (ref "R5") (pin "4") (pinfunction "4_4") (pintype "bidirectional"))
    )
    (net (code "27") (name "Net-(AUX2-Pad3)") (class "Default")
      (node (ref "AUX2") (pin "3") (pinfunction "3_3") (pintype "bidirectional"))
      (node (ref "D6") (pin "4") (pinfunction "4_4") (pintype "bidirectional"))
      (node (ref "R5") (pin "2") (pinfunction "2_2") (pintype "bidirectional"))
    )
    (net (code "28") (name "Net-(AUX2-Pad4)") (class "Default")
      (node (ref "AUX2") (pin "4") (pinfunction "4_4") (pintype "bidirectional"))
      (node (ref "D6") (pin "6") (pinfunction "6_6") (pintype "bidirectional"))
      (node (ref "R5") (pin "1") (pinfunction "1_1") (pintype "bidirectional"))
    )
    (net (code "29") (name "Net-(AUX3-Pad3)") (class "Default")
      (node (ref "AUX3") (pin "3") (pinfunction "3_3") (pintype "bidirectional"))
      (node (ref "D4") (pin "6") (pinfunction "6_6") (pintype "bidirectional"))
      (node (ref "R4") (pin "2") (pinfunction "2_2") (pintype "bidirectional"))
    )
    (net (code "30") (name "Net-(AUX3-Pad4)") (class "Default")
      (node (ref "AUX3") (pin "4") (pinfunction "4_4") (pintype "bidirectional"))
      (node (ref "D4") (pin "1") (pinfunction "1_1") (pintype "bidirectional"))
      (node (ref "R4") (pin "1") (pinfunction "1_1") (pintype "bidirectional"))
    )
    (net (code "31") (name "Net-(AUX4-Pad3)") (class "Default")
      (node (ref "AUX4") (pin "3") (pinfunction "3_3") (pintype "bidirectional"))
      (node (ref "D4") (pin "4") (pinfunction "4_4") (pintype "bidirectional"))
      (node (ref "R4") (pin "3") (pinfunction "3_3") (pintype "bidirectional"))
    )
    (net (code "32") (name "Net-(AUX4-Pad4)") (class "Default")
      (node (ref "AUX4") (pin "4") (pinfunction "4_4") (pintype "bidirectional"))
      (node (ref "D4") (pin "3") (pinfunction "3_3") (pintype "bidirectional"))
      (node (ref "R4") (pin "4") (pinfunction "4_4") (pintype "bidirectional"))
    )
    (net (code "33") (name "Net-(D1-CC)") (class "Default")
      (node (ref "C1") (pin "1") (pinfunction "1_1") (pintype "passive"))
      (node (ref "D1") (pin "3") (pinfunction "CC_3") (pintype "passive"))
      (node (ref "IC6") (pin "1") (pinfunction "IN_1") (pintype "input"))
      (node (ref "IC6") (pin "3") (pinfunction "EN_3") (pintype "input"))
    )
    (net (code "34") (name "Net-(D3-Pad1)") (class "Default")
      (node (ref "D3") (pin "1") (pinfunction "1_1") (pintype "bidirectional"))
      (node (ref "IN") (pin "7") (pinfunction "7_7") (pintype "bidirectional"))
      (node (ref "R3") (pin "7") (pinfunction "7_7") (pintype "bidirectional"))
    )
    (net (code "35") (name "Net-(D3-Pad3)") (class "Default")
      (node (ref "D3") (pin "3") (pinfunction "3_3") (pintype "bidirectional"))
      (node (ref "IN") (pin "8") (pinfunction "8_8") (pintype "bidirectional"))
      (node (ref "R3") (pin "8") (pinfunction "8_8") (pintype "bidirectional"))
    )
    (net (code "36") (name "Net-(D3-Pad4)") (class "Default")
      (node (ref "D3") (pin "4") (pinfunction "4_4") (pintype "bidirectional"))
      (node (ref "IN") (pin "5") (pinfunction "5_5") (pintype "bidirectional"))
      (node (ref "R3") (pin "5") (pinfunction "5_5") (pintype "bidirectional"))
    )
    (net (code "37") (name "Net-(D3-Pad6)") (class "Default")
      (node (ref "D3") (pin "6") (pinfunction "6_6") (pintype "bidirectional"))
      (node (ref "IN") (pin "6") (pinfunction "6_6") (pintype "bidirectional"))
      (node (ref "R3") (pin "6") (pinfunction "6_6") (pintype "bidirectional"))
    )
    (net (code "38") (name "Net-(D5-Pad3)") (class "Default")
      (node (ref "D5") (pin "3") (pinfunction "3_3") (pintype "bidirectional"))
      (node (ref "IN") (pin "4") (pinfunction "4_4") (pintype "bidirectional"))
      (node (ref "R2") (pin "7") (pinfunction "7_7") (pintype "bidirectional"))
    )
    (net (code "39") (name "Net-(D5-Pad4)") (class "Default")
      (node (ref "D5") (pin "4") (pinfunction "4_4") (pintype "bidirectional"))
      (node (ref "IN") (pin "3") (pinfunction "3_3") (pintype "bidirectional"))
      (node (ref "R2") (pin "6") (pinfunction "6_6") (pintype "bidirectional"))
    )
    (net (code "40") (name "Net-(D7-Pad1)") (class "Default")
      (node (ref "D7") (pin "1") (pinfunction "1_1") (pintype "bidirectional"))
      (node (ref "ENGINE8") (pin "3") (pinfunction "3_3") (pintype "passive"))
      (node (ref "R7") (pin "8") (pinfunction "8_8") (pintype "bidirectional"))
    )
    (net (code "41") (name "Net-(D7-Pad3)") (class "Default")
      (node (ref "D7") (pin "3") (pinfunction "3_3") (pintype "bidirectional"))
      (node (ref "ENGINE7") (pin "3") (pinfunction "3_3") (pintype "passive"))
      (node (ref "R7") (pin "7") (pinfunction "7_7") (pintype "bidirectional"))
    )
    (net (code "42") (name "Net-(D7-Pad4)") (class "Default")
      (node (ref "D7") (pin "4") (pinfunction "4_4") (pintype "bidirectional"))
      (node (ref "ENGINE5") (pin "3") (pinfunction "3_3") (pintype "passive"))
      (node (ref "R7") (pin "5") (pinfunction "5_5") (pintype "bidirectional"))
    )
    (net (code "43") (name "Net-(D7-Pad6)") (class "Default")
      (node (ref "D7") (pin "6") (pinfunction "6_6") (pintype "bidirectional"))
      (node (ref "ENGINE6") (pin "3") (pinfunction "3_3") (pintype "passive"))
      (node (ref "R7") (pin "6") (pinfunction "6_6") (pintype "bidirectional"))
    )
    (net (code "44") (name "Net-(D8-Pad1)") (class "Default")
      (node (ref "D8") (pin "1") (pinfunction "1_1") (pintype "bidirectional"))
      (node (ref "ENGINE2") (pin "3") (pinfunction "3_3") (pintype "passive"))
      (node (ref "R6") (pin "6") (pinfunction "6_6") (pintype "bidirectional"))
    )
    (net (code "45") (name "Net-(D8-Pad3)") (class "Default")
      (node (ref "D8") (pin "3") (pinfunction "3_3") (pintype "bidirectional"))
      (node (ref "ENGINE1") (pin "3") (pinfunction "3_3") (pintype "passive"))
      (node (ref "R6") (pin "5") (pinfunction "5_5") (pintype "bidirectional"))
    )
    (net (code "46") (name "Net-(D8-Pad4)") (class "Default")
      (node (ref "D8") (pin "4") (pinfunction "4_4") (pintype "bidirectional"))
      (node (ref "ENGINE3") (pin "3") (pinfunction "3_3") (pintype "passive"))
      (node (ref "R6") (pin "7") (pinfunction "7_7") (pintype "bidirectional"))
    )
    (net (code "47") (name "Net-(D8-Pad6)") (class "Default")
      (node (ref "D8") (pin "6") (pinfunction "6_6") (pintype "bidirectional"))
      (node (ref "ENGINE4") (pin "3") (pinfunction "3_3") (pintype "passive"))
      (node (ref "R6") (pin "8") (pinfunction "8_8") (pintype "bidirectional"))
    )
    (net (code "48") (name "Net-(ERR-PadA)") (class "Default")
      (node (ref "ERR") (pin "A") (pinfunction "A_A") (pintype "passive"))
      (node (ref "R1") (pin "5") (pinfunction "5_5") (pintype "bidirectional"))
    )
    (net (code "49") (name "Net-(IC1A-BOOT0)") (class "Default")
      (node (ref "IC1") (pin "60") (pinfunction "BOOT0_60") (pintype "bidirectional"))
      (node (ref "R11") (pin "2") (pinfunction "2_2") (pintype "passive"))
    )
    (net (code "50") (name "Net-(IC1A-PH0{slash}OSC_IN)") (class "Default")
      (node (ref "C21") (pin "2") (pinfunction "2_2") (pintype "passive"))
      (node (ref "IC1") (pin "5") (pinfunction "PH0/OSC_IN_5") (pintype "bidirectional"))
      (node (ref "Q1") (pin "3") (pinfunction "2_3") (pintype "passive"))
    )
    (net (code "51") (name "Net-(IC1A-PH1{slash}OSC_OUT)") (class "Default")
      (node (ref "C20") (pin "2") (pinfunction "2_2") (pintype "passive"))
      (node (ref "IC1") (pin "6") (pinfunction "PH1/OSC_OUT_6") (pintype "bidirectional"))
      (node (ref "Q1") (pin "1") (pinfunction "1_1") (pintype "passive"))
    )
    (net (code "52") (name "Net-(IC1B-PA9{slash}USART1_TX{slash}TIM1_CH2{slash}I2C3_SMBA{slash}OTG_FS_VBUS)") (class "Default")
      (node (ref "IC1") (pin "42") (pinfunction "PA9/USART1_TX/TIM1_CH2/I2C3_SMBA/OTG_FS_VBUS_42") (pintype "bidirectional"))
      (node (ref "R13") (pin "1") (pinfunction "1_1") (pintype "passive"))
    )
    (net (code "53") (name "Net-(IC1C-PB14{slash}SPI2_MISO{slash}TIM12_CH1)") (class "Default")
      (node (ref "IC1") (pin "35") (pinfunction "PB14/SPI2_MISO/TIM12_CH1_35") (pintype "bidirectional"))
      (node (ref "R8") (pin "2") (pinfunction "2_2") (pintype "bidirectional"))
    )
    (net (code "54") (name "Net-(IC1C-PB15{slash}SPI2_MOSI{slash}TIM12_CH2)") (class "Default")
      (node (ref "IC1") (pin "36") (pinfunction "PB15/SPI2_MOSI/TIM12_CH2_36") (pintype "bidirectional"))
      (node (ref "R8") (pin "1") (pinfunction "1_1") (pintype "bidirectional"))
    )
    (net (code "55") (name "Net-(IC1D-PC0{slash}ADC123_IN10)") (class "Default")
      (node (ref "IC1") (pin "8") (pinfunction "PC0/ADC123_IN10_8") (pintype "bidirectional"))
      (node (ref "R1") (pin "4") (pinfunction "4_4") (pintype "bidirectional"))
    )
    (net (code "56") (name "Net-(IC1D-PC1{slash}ADC123_IN11)") (class "Default")
      (node (ref "IC1") (pin "9") (pinfunction "PC1/ADC123_IN11_9") (pintype "bidirectional"))
      (node (ref "R1") (pin "3") (pinfunction "3_3") (pintype "bidirectional"))
    )
    (net (code "57") (name "Net-(IC1E-VCAP1)") (class "Default")
      (node (ref "C24") (pin "1") (pinfunction "1_1") (pintype "passive"))
      (node (ref "IC1") (pin "31") (pinfunction "VCAP1_31") (pintype "bidirectional"))
    )
    (net (code "58") (name "Net-(IC1E-VCAP2)") (class "Default")
      (node (ref "C23") (pin "1") (pinfunction "1_1") (pintype "passive"))
      (node (ref "IC1") (pin "47") (pinfunction "VCAP2_47") (pintype "bidirectional"))
    )
    (net (code "59") (name "Net-(IC3-C1)") (class "Default")
      (node (ref "C27") (pin "1") (pinfunction "1_1") (pintype "passive"))
      (node (ref "IC3") (pin "10") (pinfunction "C1_10") (pintype "bidirectional"))
    )
    (net (code "60") (name "Net-(IC3-SETC)") (class "Default")
      (node (ref "C22") (pin "2") (pinfunction "2_2") (pintype "passive"))
      (node (ref "IC3") (pin "12") (pinfunction "SETC_12") (pintype "bidirectional"))
    )
    (net (code "61") (name "Net-(IC3-SETP)") (class "Default")
      (node (ref "C22") (pin "1") (pinfunction "1_1") (pintype "passive"))
      (node (ref "IC3") (pin "8") (pinfunction "SETP_8") (pintype "bidirectional"))
    )
    (net (code "62") (name "Net-(IC4-REGOUT)") (class "Default")
      (node (ref "C16") (pin "1") (pinfunction "1_1") (pintype "passive"))
      (node (ref "IC4") (pin "10") (pinfunction "REGOUT_10") (pintype "bidirectional"))
    )
    (net (code "63") (name "Net-(IC7-ANT)") (class "Default")
      (node (ref "IC7") (pin "9") (pinfunction "ANT_9") (pintype "bidirectional"))
      (node (ref "MMCX1") (pin "S") (pinfunction "SIGNAL_S") (pintype "bidirectional"))
    )
    (net (code "64") (name "Net-(LINK-PadA)") (class "Default")
      (node (ref "LINK") (pin "A") (pinfunction "A_A") (pintype "passive"))
      (node (ref "R8") (pin "7") (pinfunction "7_7") (pintype "bidirectional"))
    )
    (net (code "65") (name "Net-(PWR-PadA)") (class "Default")
      (node (ref "PWR") (pin "A") (pinfunction "A_A") (pintype "passive"))
      (node (ref "R2") (pin "5") (pinfunction "5_5") (pintype "bidirectional"))
    )
    (net (code "66") (name "Net-(R1-Pad6)") (class "Default")
      (node (ref "R1") (pin "6") (pinfunction "6_6") (pintype "bidirectional"))
      (node (ref "USR") (pin "A") (pinfunction "A_A") (pintype "passive"))
    )
    (net (code "67") (name "Net-(R8-Pad8)") (class "Default")
      (node (ref "R8") (pin "8") (pinfunction "8_8") (pintype "bidirectional"))
      (node (ref "TX") (pin "A") (pinfunction "A_A") (pintype "passive"))
    )
    (net (code "68") (name "Net-(USB1-D+)") (class "Default")
      (node (ref "D2") (pin "6") (pinfunction "6_6") (pintype "bidirectional"))
      (node (ref "R10") (pin "2") (pinfunction "2_2") (pintype "passive"))
      (node (ref "USB1") (pin "3") (pinfunction "D+_3") (pintype "bidirectional"))
    )
    (net (code "69") (name "Net-(USB1-D-)") (class "Default")
      (node (ref "D2") (pin "1") (pinfunction "1_1") (pintype "bidirectional"))
      (node (ref "R9") (pin "2") (pinfunction "2_2") (pintype "passive"))
      (node (ref "USB1") (pin "2") (pinfunction "D-_2") (pintype "bidirectional"))
    )
    (net (code "70") (name "RC_5V_FILT") (class "Default")
      (node (ref "D1") (pin "1") (pinfunction "A1_1") (pintype "passive"))
      (node (ref "D7") (pin "2") (pinfunction "2_2") (pintype "bidirectional"))
      (node (ref "L3") (pin "2") (pinfunction "2_2") (pintype "passive"))
    )
    (net (code "71") (name "RF_IRQ1") (class "Default")
      (node (ref "IC1") (pin "43") (pinfunction "PA10/USART1_RX/TIM1_CH3/OTG_FS_ID_43") (pintype "bidirectional"))
      (node (ref "IC7") (pin "14") (pinfunction "DIO0_14") (pintype "bidirectional"))
    )
    (net (code "72") (name "RF_IRQ2") (class "Default")
      (node (ref "IC1") (pin "26") (pinfunction "PB0/TIM3_CH3/ADC12_IN8_26") (pintype "bidirectional"))
      (node (ref "IC7") (pin "15") (pinfunction "DIO1_15") (pintype "bidirectional"))
    )
    (net (code "73") (name "RF_MISO") (class "Default")
      (node (ref "IC1") (pin "22") (pinfunction "PA6/SPI1_MISO/TIM13_CH1/TIM3_CH1/ADC12_IN6_22") (pintype "bidirectional"))
      (node (ref "IC5") (pin "2") (pinfunction "MISO_2") (pintype "bidirectional"))
      (node (ref "IC7") (pin "2") (pinfunction "MISO_2") (pintype "bidirectional"))
    )
    (net (code "74") (name "RF_MOSI") (class "Default")
      (node (ref "IC1") (pin "23") (pinfunction "PA7/SPI1_MOSI/TIM14_CH1/TIM3_CH2/ADC12_IN7_23") (pintype "bidirectional"))
      (node (ref "IC5") (pin "5") (pinfunction "MOSI_5") (pintype "bidirectional"))
      (node (ref "IC7") (pin "3") (pinfunction "MOSI_3") (pintype "bidirectional"))
    )
    (net (code "75") (name "RF_RESET") (class "Default")
      (node (ref "IC1") (pin "4") (pinfunction "PC15/OSC32_OUT_4") (pintype "bidirectional"))
      (node (ref "IC7") (pin "6") (pinfunction "RESET_6") (pintype "bidirectional"))
    )
    (net (code "76") (name "RF_SCLK") (class "Default")
      (node (ref "IC1") (pin "21") (pinfunction "PA5/SPI1_SCK/ADC12_IN5/DAC2_OUT_21") (pintype "bidirectional"))
      (node (ref "IC5") (pin "6") (pinfunction "SCK_6") (pintype "bidirectional"))
      (node (ref "IC7") (pin "4") (pinfunction "SCK_4") (pintype "bidirectional"))
    )
    (net (code "77") (name "RF_SEL") (class "Default")
      (node (ref "IC1") (pin "20") (pinfunction "PA4/SPI1_NSS/SPI3_NSS/ADC12_IN4/DAC1_OUT_20") (pintype "bidirectional"))
      (node (ref "IC7") (pin "5") (pinfunction "~{CS}_5") (pintype "bidirectional"))
    )
    (net (code "78") (name "RXD3") (class "Default")
      (node (ref "IC1") (pin "52") (pinfunction "PC11/SPI3_MISO/UART4_RX/USART3_RX_52") (pintype "bidirectional"))
      (node (ref "R5") (pin "5") (pinfunction "5_5") (pintype "bidirectional"))
    )
    (net (code "79") (name "RXD4") (class "Default")
      (node (ref "IC1") (pin "15") (pinfunction "PA1/USART4_RX/TIM5_CH2/TIM2_CH2/ADC123_IN1_15") (pintype "bidirectional"))
      (node (ref "R4") (pin "8") (pinfunction "8_8") (pintype "bidirectional"))
    )
    (net (code "80") (name "RXD5") (class "Default")
      (node (ref "IC1") (pin "54") (pinfunction "PD2/UART5_RX_54") (pintype "bidirectional"))
      (node (ref "R5") (pin "8") (pinfunction "8_8") (pintype "bidirectional"))
    )
    (net (code "81") (name "SCL") (class "Default")
      (node (ref "IC1") (pin "29") (pinfunction "PB10/SPI2_SCK/I2C2_SCL/USART3_TX/TIM2_CH3_29") (pintype "bidirectional"))
      (node (ref "IC2") (pin "8") (pinfunction "SCLK_8") (pintype "bidirectional"))
      (node (ref "IC3") (pin "1") (pinfunction "SCL/SCLK_1") (pintype "bidirectional"))
      (node (ref "IC4") (pin "23") (pinfunction "SCL/SCLK_23") (pintype "bidirectional"))
      (node (ref "R15") (pin "2") (pinfunction "2_2") (pintype "passive"))
      (node (ref "TEST2") (pin "1") (pinfunction "2_1") (pintype "passive"))
    )
    (net (code "82") (name "SDA") (class "Default")
      (node (ref "IC1") (pin "30") (pinfunction "PB11/I2C2_SDA/USART3_RX/TIM2_CH4_30") (pintype "bidirectional"))
      (node (ref "IC2") (pin "7") (pinfunction "SDA/SDI_7") (pintype "bidirectional"))
      (node (ref "IC3") (pin "16") (pinfunction "SDA/MOSI_16") (pintype "bidirectional"))
      (node (ref "IC4") (pin "24") (pinfunction "SDA/SDI_24") (pintype "bidirectional"))
      (node (ref "R14") (pin "2") (pinfunction "2_2") (pintype "passive"))
      (node (ref "TEST1") (pin "1") (pinfunction "2_1") (pintype "passive"))
    )
    (net (code "83") (name "SWCLK") (class "Default")
      (node (ref "IC1") (pin "49") (pinfunction "PA14/JTCK-SWCLK_49") (pintype "bidirectional"))
      (node (ref "SWD") (pin "1") (pinfunction "1_1") (pintype "bidirectional"))
    )
    (net (code "84") (name "SWDIO") (class "Default")
      (node (ref "IC1") (pin "46") (pinfunction "PA13/JTMS-SWDIO_46") (pintype "bidirectional"))
      (node (ref "SWD") (pin "2") (pinfunction "2_2") (pintype "bidirectional"))
    )
    (net (code "85") (name "TXD3") (class "Default")
      (node (ref "IC1") (pin "51") (pinfunction "PC10/SPI3_SCK/UART4_TX/USART3_TX_51") (pintype "bidirectional"))
      (node (ref "R5") (pin "6") (pinfunction "6_6") (pintype "bidirectional"))
    )
    (net (code "86") (name "TXD4") (class "Default")
      (node (ref "IC1") (pin "14") (pinfunction "PA0/USART4_TX/TIM5_CH1/ADC123_IN0/WKUP_14") (pintype "bidirectional"))
      (node (ref "R4") (pin "7") (pinfunction "7_7") (pintype "bidirectional"))
    )
    (net (code "87") (name "TXD5") (class "Default")
      (node (ref "IC1") (pin "53") (pinfunction "PC12/UART5_TX/SPI3_MOSI_53") (pintype "bidirectional"))
      (node (ref "R5") (pin "7") (pinfunction "7_7") (pintype "bidirectional"))
    )
    (net (code "88") (name "USB_5V_FILT") (class "Default")
      (node (ref "D1") (pin "2") (pinfunction "A2_2") (pintype "passive"))
      (node (ref "L2") (pin "2") (pinfunction "2_2") (pintype "passive"))
      (node (ref "R13") (pin "2") (pinfunction "2_2") (pintype "passive"))
    )
    (net (code "89") (name "VCC") (class "Default")
      (node (ref "D2") (pin "2") (pinfunction "2_2") (pintype "bidirectional"))
      (node (ref "L2") (pin "1") (pinfunction "1_1") (pintype "passive"))
      (node (ref "USB1") (pin "1") (pinfunction "VBUS_1") (pintype "bidirectional"))
    )
    (net (code "90") (name "VCCA") (class "Default")
      (node (ref "C13") (pin "1") (pinfunction "1_1") (pintype "passive"))
      (node (ref "C14") (pin "1") (pinfunction "1_1") (pintype "passive"))
      (node (ref "C15") (pin "1") (pinfunction "1_1") (pintype "passive"))
      (node (ref "C17") (pin "1") (pinfunction "1_1") (pintype "passive"))
      (node (ref "C19") (pin "1") (pinfunction "1_1") (pintype "passive"))
      (node (ref "C2") (pin "1") (pinfunction "1_1") (pintype "passive"))
      (node (ref "IC2") (pin "1") (pinfunction "VCC_1") (pintype "bidirectional"))
      (node (ref "IC2") (pin "2") (pinfunction "PS_2") (pintype "bidirectional"))
      (node (ref "IC3") (pin "13") (pinfunction "VDDIO_13") (pintype "bidirectional"))
      (node (ref "IC3") (pin "2") (pinfunction "VDD_2") (pintype "bidirectional"))
      (node (ref "IC3") (pin "4") (pinfunction "~{CS}_4") (pintype "bidirectional"))
      (node (ref "IC3") (pin "6") (pinfunction "I2C/~{SPI}_6") (pintype "bidirectional"))
      (node (ref "IC4") (pin "13") (pinfunction "VDD_13") (pintype "power_in"))
      (node (ref "IC4") (pin "22") (pinfunction "~{CS}_22") (pintype "bidirectional"))
      (node (ref "IC4") (pin "8") (pinfunction "VDDIO_8") (pintype "power_in"))
      (node (ref "IC4") (pin "9") (pinfunction "AD0/SDO_9") (pintype "bidirectional"))
      (node (ref "L1") (pin "2") (pinfunction "2_2") (pintype "passive"))
    )
    (net (code "91") (name "unconnected-(D2-Pad3)") (class "Default")
      (node (ref "D2") (pin "3") (pinfunction "3_3") (pintype "bidirectional"))
    )
    (net (code "92") (name "unconnected-(D2-Pad4)") (class "Default")
      (node (ref "D2") (pin "4") (pinfunction "4_4") (pintype "bidirectional"))
    )
    (net (code "93") (name "unconnected-(D3-Pad2)") (class "Default")
      (node (ref "D3") (pin "2") (pinfunction "2_2") (pintype "bidirectional"))
    )
    (net (code "94") (name "unconnected-(D4-Pad2)") (class "Default")
      (node (ref "D4") (pin "2") (pinfunction "2_2") (pintype "bidirectional"))
    )
    (net (code "95") (name "unconnected-(D5-Pad1)") (class "Default")
      (node (ref "D5") (pin "1") (pinfunction "1_1") (pintype "bidirectional"))
    )
    (net (code "96") (name "unconnected-(D5-Pad2)") (class "Default")
      (node (ref "D5") (pin "2") (pinfunction "2_2") (pintype "bidirectional"))
    )
    (net (code "97") (name "unconnected-(D5-Pad6)") (class "Default")
      (node (ref "D5") (pin "6") (pinfunction "6_6") (pintype "bidirectional"))
    )
    (net (code "98") (name "unconnected-(D6-Pad2)") (class "Default")
      (node (ref "D6") (pin "2") (pinfunction "2_2") (pintype "bidirectional"))
    )
    (net (code "99") (name "unconnected-(D8-Pad2)") (class "Default")
      (node (ref "D8") (pin "2") (pinfunction "2_2") (pintype "bidirectional"))
    )
    (net (code "100") (name "unconnected-(IC1B-PA15{slash}JTDI{slash}SPI3_NSS{slash}I2S3_WS{slash}SPI1_NSS-Pad50)") (class "Default")
      (node (ref "IC1") (pin "50") (pinfunction "PA15/JTDI/SPI3_NSS/I2S3_WS/SPI1_NSS_50") (pintype "bidirectional"))
    )
    (net (code "101") (name "unconnected-(IC1C-PB1{slash}TIM3_CH4{slash}ADC12_IN9-Pad27)") (class "Default")
      (node (ref "IC1") (pin "27") (pinfunction "PB1/TIM3_CH4/ADC12_IN9_27") (pintype "bidirectional"))
    )
    (net (code "102") (name "unconnected-(IC1C-PB2{slash}BOOT1-Pad28)") (class "Default")
      (node (ref "IC1") (pin "28") (pinfunction "PB2/BOOT1_28") (pintype "bidirectional"))
    )
    (net (code "103") (name "unconnected-(IC1D-PC2{slash}SPI2_MISO{slash}ADC123_IN12-Pad10)") (class "Default")
      (node (ref "IC1") (pin "10") (pinfunction "PC2/SPI2_MISO/ADC123_IN12_10") (pintype "bidirectional"))
    )
    (net (code "104") (name "unconnected-(IC1D-PC3{slash}SPI2_MOSI{slash}ADC123_IN13-Pad11)") (class "Default")
      (node (ref "IC1") (pin "11") (pinfunction "PC3/SPI2_MOSI/ADC123_IN13_11") (pintype "bidirectional"))
    )
    (net (code "105") (name "unconnected-(IC1D-PC5{slash}ADC12_IN15-Pad25)") (class "Default")
      (node (ref "IC1") (pin "25") (pinfunction "PC5/ADC12_IN15_25") (pintype "bidirectional"))
    )
    (net (code "106") (name "unconnected-(IC2-SDO-Pad6)") (class "Default")
      (node (ref "IC2") (pin "6") (pinfunction "SDO_6") (pintype "bidirectional"))
    )
    (net (code "107") (name "unconnected-(IC3-MISO-Pad5)") (class "Default")
      (node (ref "IC3") (pin "5") (pinfunction "MISO_5") (pintype "bidirectional"))
    )
    (net (code "108") (name "unconnected-(IC4-AUX_CL-Pad7)") (class "Default")
      (node (ref "IC4") (pin "7") (pinfunction "AUX_CL_7") (pintype "bidirectional"))
    )
    (net (code "109") (name "unconnected-(IC4-AUX_DA-Pad21)") (class "Default")
      (node (ref "IC4") (pin "21") (pinfunction "AUX_DA_21") (pintype "bidirectional"))
    )
    (net (code "110") (name "unconnected-(IC6-BP-Pad4)") (class "Default")
      (node (ref "IC6") (pin "4") (pinfunction "BP_4") (pintype "input"))
    )
    (net (code "111") (name "unconnected-(IC7-DIO2-Pad16)") (class "Default")
      (node (ref "IC7") (pin "16") (pinfunction "DIO2_16") (pintype "bidirectional"))
    )
    (net (code "112") (name "unconnected-(IC7-DIO3-Pad11)") (class "Default")
      (node (ref "IC7") (pin "11") (pinfunction "DIO3_11") (pintype "bidirectional"))
    )
    (net (code "113") (name "unconnected-(IC7-DIO4-Pad12)") (class "Default")
      (node (ref "IC7") (pin "12") (pinfunction "DIO4_12") (pintype "bidirectional"))
    )
    (net (code "114") (name "unconnected-(IC7-DIO5-Pad7)") (class "Default")
      (node (ref "IC7") (pin "7") (pinfunction "DIO5_7") (pintype "bidirectional"))
    )
    (net (code "115") (name "unconnected-(USB1-ID-Pad4)") (class "Default")
      (node (ref "USB1") (pin "4") (pinfunction "ID_4") (pintype "bidirectional"))
    )
    (net (code "116") (name "~{SRST}") (class "Default")
      (node (ref "C18") (pin "1") (pinfunction "1_1") (pintype "passive"))
      (node (ref "IC1") (pin "7") (pinfunction "~{NRST}_7") (pintype "bidirectional"))
      (node (ref "R12") (pin "2") (pinfunction "2_2") (pintype "passive"))
      (node (ref "SWD") (pin "3") (pinfunction "3_3") (pintype "bidirectional"))
    )
  )
)
